# SB_PSU.net
KiCad netlist of a schematic drawn in Altium Designer
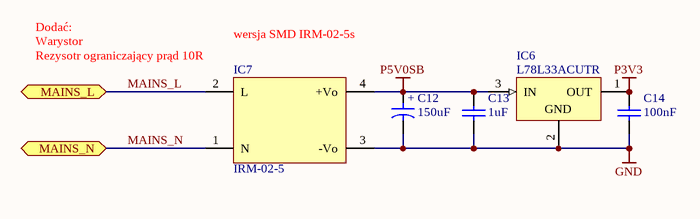
[diagram p0: SB_PSU.SchDoc]

(export (version "E")
  (design (tool "Eeschema 10.0.6"))
  (components
    (comp (ref "C12")
      (value "150uF")
      (footprint "CAPPR500-1050X800")
      (description "Polarised capacitor")
      (fields
        (field (name "PART NUMBER") "CAER_150UF_16V_20%_SANYO_16SEQP150M")
        (field (name "VOLTAGE") "16V")
        (field (name "AUTHOR") "CERN DEM JLC")
      )
      (libsource (lib "Capacitors") (part "Capacitor - polarized"))
    )
    (comp (ref "C13")
      (value "1uF")
      (footprint "CAPC1608X87N")
      (description "Non-polarised capacitor")
      (fields
        (field (name "PART NUMBER") "CC0603_1UF_16V_10%_X7R")
        (field (name "VOLTAGE") "16V")
        (field (name "AUTHOR") "CERN DEM JLC")
      )
      (libsource (lib "Capacitors") (part "Capacitor - non polarized"))
    )
    (comp (ref "C14")
      (value "100nF")
      (footprint "CAPC1608X87N")
      (description "Non-polarised capacitor")
      (fields
        (field (name "PART NUMBER") "CC0603_100NF_50V_10%_X5R")
        (field (name "VOLTAGE") "50V")
        (field (name "AUTHOR") "CERN DEM MR")
      )
      (libsource (lib "Capacitors") (part "Capacitor - non polarized"))
    )
    (comp (ref "IC6")
      (value "L78L33ACUTR")
      (footprint "SOT89")
      (description "3-Terminal Regulator 1=OUT 2=GND 3=IN")
      (fields (field (name "MANUFACTURER") "ST MICROELECTRONICS") (field (name "AUTHOR") "CERN DEM JLC"))
      (libsource (lib "ICs And Semiconductors") (part "REG3 1OUT-2GND-3IN"))
    )
    (comp (ref "IC7")
      (value "IRM-02-5")
      (footprint "PWS_MEANWELL_IRM-02")
      (description "Power Supply")
      (fields (field (name "MANUFACTURER") "MEAN WELL") (field (name "AUTHOR") "GK"))
      (libsource (lib "Regulators_SMPS") (part "AC_DC_IRM-02-5"))
    )
  )
  (nets
    (net (code "1") (name "/MAINS_L") (class "Default")
      (node (ref "IC7") (pin "2") (pinfunction "L_2") (pintype "power_in"))
    )
    (net (code "2") (name "/MAINS_N") (class "Default")
      (node (ref "IC7") (pin "1") (pinfunction "N_1") (pintype "power_in"))
    )
    (net (code "3") (name "GND") (class "Default")
      (node (ref "C12") (pin "2") (pinfunction "2_2") (pintype "passive"))
      (node (ref "C13") (pin "1") (pinfunction "1_1") (pintype "passive"))
      (node (ref "C14") (pin "2") (pinfunction "2_2") (pintype "passive"))
      (node (ref "IC6") (pin "2") (pinfunction "GND_2") (pintype "power_in"))
      (node (ref "IC7") (pin "3") (pinfunction "-Vo_3") (pintype "power_in"))
    )
    (net (code "4") (name "P3V3") (class "Default")
      (node (ref "C14") (pin "1") (pinfunction "1_1") (pintype "passive"))
      (node (ref "IC6") (pin "1") (pinfunction "OUT_1") (pintype "power_in"))
    )
    (net (code "5") (name "P5V0SB") (class "Default")
      (node (ref "C12") (pin "1") (pinfunction "1_1") (pintype "passive"))
      (node (ref "C13") (pin "2") (pinfunction "2_2") (pintype "passive"))
      (node (ref "IC6") (pin "3") (pinfunction "IN_3") (pintype "input"))
      (node (ref "IC7") (pin "4") (pinfunction "+Vo_4") (pintype "power_in"))
    )
  )
)
